# Adafruit_TPA2016D2.net
KiCad netlist of a schematic drawn in EAGLE
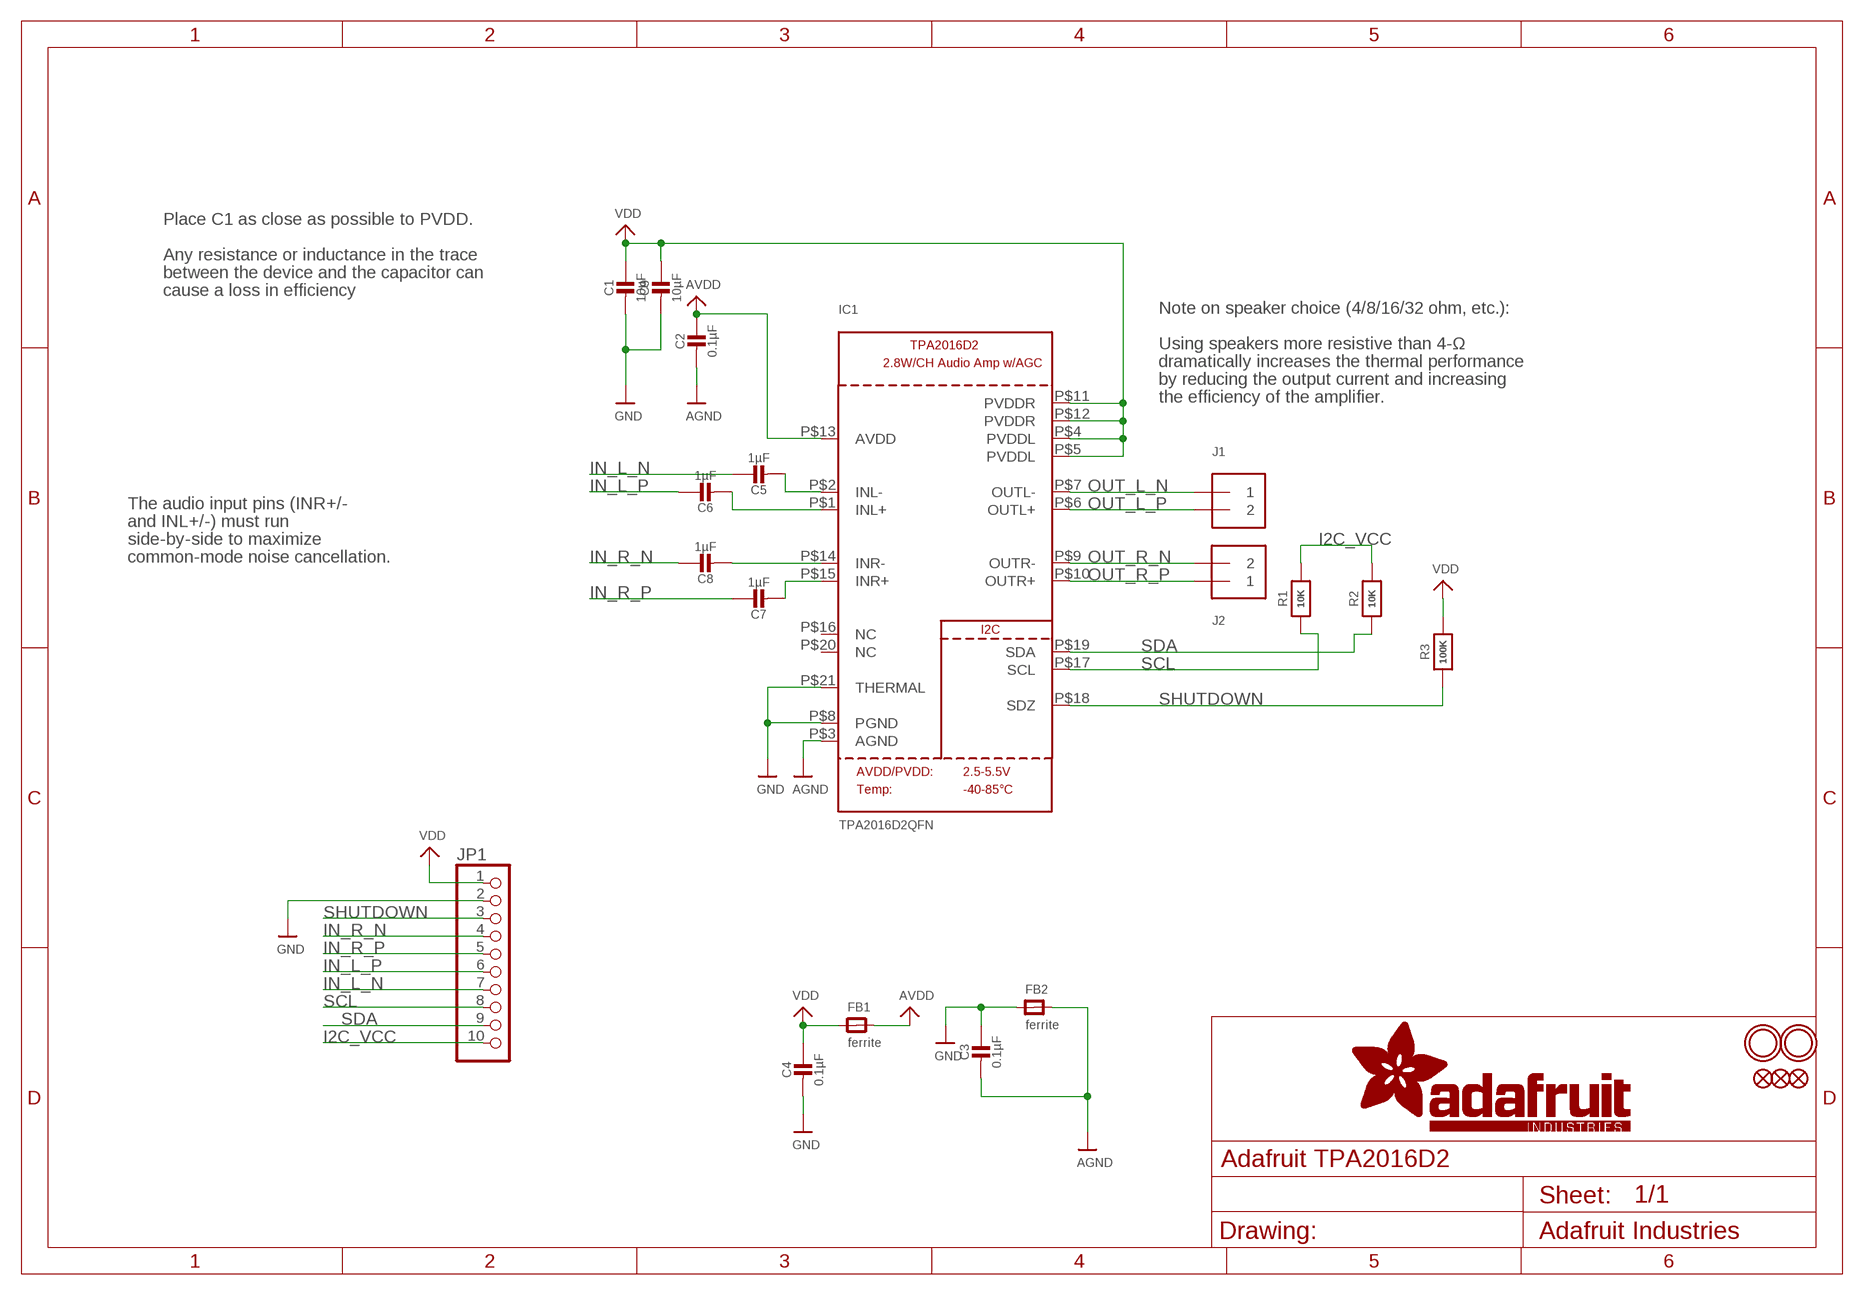
[diagram p0: schematic, sheet 1]

(export (version "E")
  (design (tool "Eeschema 10.0.6"))
  (components
    (comp (ref "C1")
      (value "10µF")
      (footprint "eagle-import:0805-NO")
      (libsource (lib "eagle-import") (part "CAP_CERAMIC0805-NOOUTLINE"))
    )
    (comp (ref "C2")
      (value "0.1µF")
      (footprint "eagle-import:0805-NO")
      (libsource (lib "eagle-import") (part "CAP_CERAMIC0805-NOOUTLINE"))
    )
    (comp (ref "C3")
      (value "0.1µF")
      (footprint "eagle-import:0805-NO")
      (libsource (lib "eagle-import") (part "CAP_CERAMIC0805-NOOUTLINE"))
    )
    (comp (ref "C4")
      (value "0.1µF")
      (footprint "eagle-import:0805-NO")
      (libsource (lib "eagle-import") (part "CAP_CERAMIC0805-NOOUTLINE"))
    )
    (comp (ref "C5")
      (value "1µF")
      (footprint "eagle-import:0805-NO")
      (libsource (lib "eagle-import") (part "CAP_CERAMIC0805-NOOUTLINE"))
    )
    (comp (ref "C6")
      (value "1µF")
      (footprint "eagle-import:0805-NO")
      (libsource (lib "eagle-import") (part "CAP_CERAMIC0805-NOOUTLINE"))
    )
    (comp (ref "C7")
      (value "1µF")
      (footprint "eagle-import:0805-NO")
      (libsource (lib "eagle-import") (part "CAP_CERAMIC0805-NOOUTLINE"))
    )
    (comp (ref "C8")
      (value "1µF")
      (footprint "eagle-import:0805-NO")
      (libsource (lib "eagle-import") (part "CAP_CERAMIC0805-NOOUTLINE"))
    )
    (comp (ref "C9")
      (value "10µF")
      (footprint "eagle-import:0805-NO")
      (libsource (lib "eagle-import") (part "CAP_CERAMIC0805-NOOUTLINE"))
    )
    (comp (ref "FB1")
      (value "ferrite")
      (footprint "eagle-import:_0805MP")
      (libsource (lib "eagle-import") (part "FERRITE_0805MP"))
    )
    (comp (ref "FB2")
      (value "ferrite")
      (footprint "eagle-import:_0805MP")
      (libsource (lib "eagle-import") (part "FERRITE_0805MP"))
    )
    (comp (ref "FID1")
      (value "FIDUCIAL\"\"")
      (footprint "eagle-import:FIDUCIAL_1MM")
      (libsource (lib "eagle-import") (part "FIDUCIAL{dblquote}{dblquote}"))
    )
    (comp (ref "FID2")
      (value "FIDUCIAL\"\"")
      (footprint "eagle-import:FIDUCIAL_1MM")
      (libsource (lib "eagle-import") (part "FIDUCIAL{dblquote}{dblquote}"))
    )
    (comp (ref "FID3")
      (value "FIDUCIAL\"\"")
      (footprint "eagle-import:FIDUCIAL_1MM")
      (fields (field (name "BOM") "EXCLUDE"))
      (libsource (lib "eagle-import") (part "FIDUCIAL{dblquote}{dblquote}"))
    )
    (comp (ref "IC1")
      (value "TPA2016D2QFN")
      (footprint "eagle-import:QFN20_4MM")
      (libsource (lib "eagle-import") (part "TPA2016D2QFN"))
    )
    (comp (ref "J1")
      (value "TERMBLOCK_1X2")
      (footprint "eagle-import:TERMBLOCK_1X2-3.5MM")
      (libsource (lib "eagle-import") (part "TERMBLOCK_1X2"))
    )
    (comp (ref "J2")
      (value "TERMBLOCK_1X2")
      (footprint "eagle-import:TERMBLOCK_1X2-3.5MM")
      (libsource (lib "eagle-import") (part "TERMBLOCK_1X2"))
    )
    (comp (ref "JP1")
      (value "HEADER-1X1070MIL")
      (footprint "eagle-import:1X10_ROUND70")
      (libsource (lib "eagle-import") (part "HEADER-1X1070MIL"))
    )
    (comp (ref "R1")
      (value "10K")
      (footprint "eagle-import:0805-NO")
      (libsource (lib "eagle-import") (part "RESISTOR0805_NOOUTLINE"))
    )
    (comp (ref "R2")
      (value "10K")
      (footprint "eagle-import:0805-NO")
      (libsource (lib "eagle-import") (part "RESISTOR0805_NOOUTLINE"))
    )
    (comp (ref "R3")
      (value "100K")
      (footprint "eagle-import:0805-NO")
      (libsource (lib "eagle-import") (part "RESISTOR0805_NOOUTLINE"))
    )
    (comp (ref "U$20")
      (value "MOUNTINGHOLE2.5_THICK")
      (footprint "eagle-import:MOUNTINGHOLE_2.5_PLATED_THICK")
      (libsource (lib "eagle-import") (part "MOUNTINGHOLE2.5_THICK"))
    )
    (comp (ref "U$21")
      (value "MOUNTINGHOLE2.5_THICK")
      (footprint "eagle-import:MOUNTINGHOLE_2.5_PLATED_THICK")
      (libsource (lib "eagle-import") (part "MOUNTINGHOLE2.5_THICK"))
    )
  )
  (nets
    (net (code "1") (name "/I2C_VCC") (class "Default")
      (node (ref "JP1") (pin "10") (pinfunction "10_10") (pintype "passive"))
      (node (ref "R1") (pin "2") (pinfunction "2_2") (pintype "passive"))
      (node (ref "R2") (pin "2") (pinfunction "2_2") (pintype "passive"))
    )
    (net (code "2") (name "/IN_L_N") (class "Default")
      (node (ref "C5") (pin "1") (pinfunction "1_1") (pintype "passive"))
      (node (ref "JP1") (pin "7") (pinfunction "7_7") (pintype "passive"))
    )
    (net (code "3") (name "/IN_L_P") (class "Default")
      (node (ref "C6") (pin "1") (pinfunction "1_1") (pintype "passive"))
      (node (ref "JP1") (pin "6") (pinfunction "6_6") (pintype "passive"))
    )
    (net (code "4") (name "/IN_R_N") (class "Default")
      (node (ref "C8") (pin "1") (pinfunction "1_1") (pintype "passive"))
      (node (ref "JP1") (pin "4") (pinfunction "4_4") (pintype "passive"))
    )
    (net (code "5") (name "/IN_R_P") (class "Default")
      (node (ref "C7") (pin "1") (pinfunction "1_1") (pintype "passive"))
      (node (ref "JP1") (pin "5") (pinfunction "5_5") (pintype "passive"))
    )
    (net (code "6") (name "/OUT_L_N") (class "Default")
      (node (ref "IC1") (pin "P$7") (pinfunction "OUTL-_P$7") (pintype "output"))
      (node (ref "J1") (pin "1") (pinfunction "1_1") (pintype "passive"))
    )
    (net (code "7") (name "/OUT_L_P") (class "Default")
      (node (ref "IC1") (pin "P$6") (pinfunction "OUTL+_P$6") (pintype "output"))
      (node (ref "J1") (pin "2") (pinfunction "2_2") (pintype "passive"))
    )
    (net (code "8") (name "/OUT_R_N") (class "Default")
      (node (ref "IC1") (pin "P$9") (pinfunction "OUTR-_P$9") (pintype "output"))
      (node (ref "J2") (pin "2") (pinfunction "2_2") (pintype "passive"))
    )
    (net (code "9") (name "/OUT_R_P") (class "Default")
      (node (ref "IC1") (pin "P$10") (pinfunction "OUTR+_P$10") (pintype "output"))
      (node (ref "J2") (pin "1") (pinfunction "1_1") (pintype "passive"))
    )
    (net (code "10") (name "/SCL") (class "Default")
      (node (ref "IC1") (pin "P$17") (pinfunction "SCL_P$17") (pintype "bidirectional"))
      (node (ref "JP1") (pin "8") (pinfunction "8_8") (pintype "passive"))
      (node (ref "R1") (pin "1") (pinfunction "1_1") (pintype "passive"))
    )
    (net (code "11") (name "/SDA") (class "Default")
      (node (ref "IC1") (pin "P$19") (pinfunction "SDA_P$19") (pintype "bidirectional"))
      (node (ref "JP1") (pin "9") (pinfunction "9_9") (pintype "passive"))
      (node (ref "R2") (pin "1") (pinfunction "1_1") (pintype "passive"))
    )
    (net (code "12") (name "/SHUTDOWN") (class "Default")
      (node (ref "IC1") (pin "P$18") (pinfunction "SDZ_P$18") (pintype "input"))
      (node (ref "JP1") (pin "3") (pinfunction "3_3") (pintype "passive"))
      (node (ref "R3") (pin "1") (pinfunction "1_1") (pintype "passive"))
    )
    (net (code "13") (name "AGND") (class "Default")
      (node (ref "C2") (pin "2") (pinfunction "2_2") (pintype "passive"))
      (node (ref "C3") (pin "2") (pinfunction "2_2") (pintype "passive"))
      (node (ref "FB2") (pin "2") (pinfunction "P$2_2") (pintype "passive"))
      (node (ref "IC1") (pin "P$3") (pinfunction "AGND_P$3") (pintype "power_in"))
    )
    (net (code "14") (name "AVDD") (class "Default")
      (node (ref "C2") (pin "1") (pinfunction "1_1") (pintype "passive"))
      (node (ref "FB1") (pin "2") (pinfunction "P$2_2") (pintype "passive"))
      (node (ref "IC1") (pin "P$13") (pinfunction "AVDD_P$13") (pintype "power_in"))
    )
    (net (code "15") (name "GND") (class "Default")
      (node (ref "C1") (pin "2") (pinfunction "2_2") (pintype "passive"))
      (node (ref "C3") (pin "1") (pinfunction "1_1") (pintype "passive"))
      (node (ref "C4") (pin "2") (pinfunction "2_2") (pintype "passive"))
      (node (ref "C9") (pin "2") (pinfunction "2_2") (pintype "passive"))
      (node (ref "FB2") (pin "1") (pinfunction "P$1_1") (pintype "passive"))
      (node (ref "IC1") (pin "P$21") (pinfunction "THERMAL_P$21") (pintype "bidirectional"))
      (node (ref "IC1") (pin "P$8") (pinfunction "PGND_P$8") (pintype "power_in"))
      (node (ref "JP1") (pin "2") (pinfunction "2_2") (pintype "passive"))
    )
    (net (code "16") (name "Net-(IC1-INL+)") (class "Default")
      (node (ref "C6") (pin "2") (pinfunction "2_2") (pintype "passive"))
      (node (ref "IC1") (pin "P$1") (pinfunction "INL+_P$1") (pintype "input"))
    )
    (net (code "17") (name "Net-(IC1-INL-)") (class "Default")
      (node (ref "C5") (pin "2") (pinfunction "2_2") (pintype "passive"))
      (node (ref "IC1") (pin "P$2") (pinfunction "INL-_P$2") (pintype "input"))
    )
    (net (code "18") (name "Net-(IC1-INR+)") (class "Default")
      (node (ref "C7") (pin "2") (pinfunction "2_2") (pintype "passive"))
      (node (ref "IC1") (pin "P$15") (pinfunction "INR+_P$15") (pintype "input"))
    )
    (net (code "19") (name "Net-(IC1-INR-)") (class "Default")
      (node (ref "C8") (pin "2") (pinfunction "2_2") (pintype "passive"))
      (node (ref "IC1") (pin "P$14") (pinfunction "INR-_P$14") (pintype "input"))
    )
    (net (code "20") (name "VDD") (class "Default")
      (node (ref "C1") (pin "1") (pinfunction "1_1") (pintype "passive"))
      (node (ref "C4") (pin "1") (pinfunction "1_1") (pintype "passive"))
      (node (ref "C9") (pin "1") (pinfunction "1_1") (pintype "passive"))
      (node (ref "FB1") (pin "1") (pinfunction "P$1_1") (pintype "passive"))
      (node (ref "IC1") (pin "P$11") (pinfunction "PVDDR_P$11") (pintype "power_in"))
      (node (ref "IC1") (pin "P$12") (pinfunction "PVDDR_P$12") (pintype "power_in"))
      (node (ref "IC1") (pin "P$4") (pinfunction "PVDDL_P$4") (pintype "power_in"))
      (node (ref "IC1") (pin "P$5") (pinfunction "PVDDL_P$5") (pintype "power_in"))
      (node (ref "JP1") (pin "1") (pinfunction "1_1") (pintype "passive"))
      (node (ref "R3") (pin "2") (pinfunction "2_2") (pintype "passive"))
    )
    (net (code "21") (name "unconnected-(IC1-NC-PadP$16)") (class "Default")
      (node (ref "IC1") (pin "P$16") (pinfunction "NC_P$16") (pintype "no_connect"))
    )
    (net (code "22") (name "unconnected-(IC1-NC-PadP$20)") (class "Default")
      (node (ref "IC1") (pin "P$20") (pinfunction "NC_P$20") (pintype "no_connect"))
    )
  )
)
